# USB.net
KiCad netlist of a schematic drawn in Altium Designer
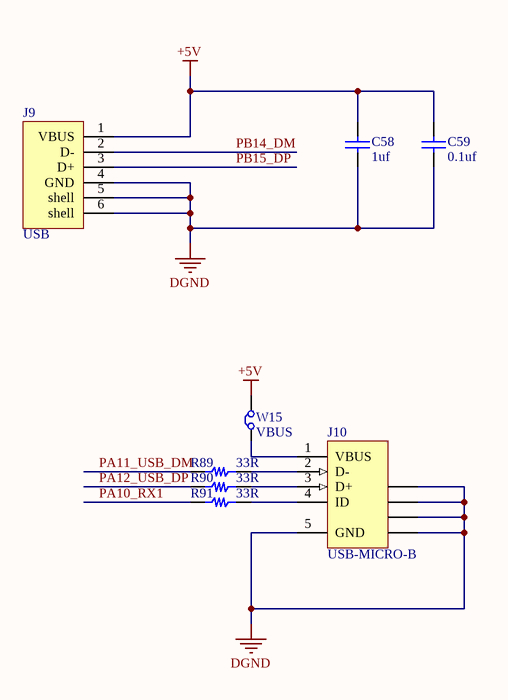
[diagram p0: USB.SchDoc]

(export (version "E")
  (design (tool "Eeschema 10.0.6"))
  (components
    (comp (ref "C58")
      (value "1uf")
      (footprint "0805C")
      (description "贴片电容")
      (fields (field (name "PUBLISHER") "Altium Limited"))
      (libsource (lib "Device_CHT") (part "Cap"))
    )
    (comp (ref "C59")
      (value "0.1uf")
      (footprint "0805C")
      (description "贴片电容")
      (fields (field (name "PUBLISHER") "Altium Limited"))
      (libsource (lib "Device_CHT") (part "Cap"))
    )
    (comp (ref "J9") (value "USB") (footprint "USB-A") (libsource (lib "Connector_Veiko") (part "USB")))
    (comp (ref "J10")
      (value "USB-MICRO-B")
      (footprint "USB-MINI-B")
      (libsource (lib "Connector_Veiko") (part "USB-MICRO-B"))
    )
    (comp (ref "R89")
      (value "33R")
      (footprint "0805_small")
      (description "电阻")
      (fields (field (name "PUBLISHER") "Altium Limited"))
      (libsource (lib "Device_CHT") (part "Res"))
    )
    (comp (ref "R90")
      (value "33R")
      (footprint "0805_small")
      (description "电阻")
      (fields (field (name "PUBLISHER") "Altium Limited"))
      (libsource (lib "Device_CHT") (part "Res"))
    )
    (comp (ref "R91")
      (value "33R")
      (footprint "0805_small")
      (description "电阻")
      (fields (field (name "PUBLISHER") "Altium Limited"))
      (libsource (lib "Device_CHT") (part "Res"))
    )
    (comp (ref "W15")
      (value "VBUS")
      (footprint "sip2-2.54mm")
      (description "Jumper Wire")
      (fields (field (name "PUBLISHER") "Altium Limited"))
      (libsource (lib "Connector_Veiko") (part "Jumper"))
    )
  )
  (nets
    (net (code "1") (name "+5V") (class "Default")
      (node (ref "C58") (pin "1") (pinfunction "1_1") (pintype "passive"))
      (node (ref "C59") (pin "1") (pinfunction "1_1") (pintype "passive"))
      (node (ref "J9") (pin "1") (pinfunction "VBUS_1") (pintype "passive"))
      (node (ref "W15") (pin "2") (pinfunction "C2_2") (pintype "passive"))
    )
    (net (code "2") (name "/PA10_RX1") (class "Default")
      (node (ref "R91") (pin "2") (pinfunction "2_2") (pintype "passive"))
    )
    (net (code "3") (name "/PA11_USB_DM") (class "Default")
      (node (ref "R89") (pin "2") (pinfunction "2_2") (pintype "passive"))
    )
    (net (code "4") (name "/PA12_USB_DP") (class "Default")
      (node (ref "R90") (pin "2") (pinfunction "2_2") (pintype "passive"))
    )
    (net (code "5") (name "/PB14_DM") (class "Default")
      (node (ref "J9") (pin "2") (pinfunction "D-_2") (pintype "passive"))
    )
    (net (code "6") (name "/PB15_DP") (class "Default")
      (node (ref "J9") (pin "3") (pinfunction "D+_3") (pintype "passive"))
    )
    (net (code "7") (name "DGND") (class "Default")
      (node (ref "C58") (pin "2") (pinfunction "2_2") (pintype "passive"))
      (node (ref "C59") (pin "2") (pinfunction "2_2") (pintype "passive"))
      (node (ref "J10") (pin "5") (pinfunction "GND_5") (pintype "passive"))
      (node (ref "J10") (pin "6") (pinfunction "SHLD_6") (pintype "passive"))
      (node (ref "J10") (pin "7") (pinfunction "SHLD_7") (pintype "passive"))
      (node (ref "J10") (pin "8") (pinfunction "SHLD_8") (pintype "passive"))
      (node (ref "J10") (pin "9") (pinfunction "SHLD_9") (pintype "passive"))
      (node (ref "J9") (pin "4") (pinfunction "GND_4") (pintype "passive"))
      (node (ref "J9") (pin "5") (pinfunction "shell_5") (pintype "passive"))
      (node (ref "J9") (pin "6") (pinfunction "shell_6") (pintype "passive"))
    )
    (net (code "8") (name "Net-(J10-D+)") (class "Default")
      (node (ref "J10") (pin "3") (pinfunction "D+_3") (pintype "input"))
      (node (ref "R90") (pin "1") (pinfunction "1_1") (pintype "passive"))
    )
    (net (code "9") (name "Net-(J10-D-)") (class "Default")
      (node (ref "J10") (pin "2") (pinfunction "D-_2") (pintype "input"))
      (node (ref "R89") (pin "1") (pinfunction "1_1") (pintype "passive"))
    )
    (net (code "10") (name "Net-(J10-ID)") (class "Default")
      (node (ref "J10") (pin "4") (pinfunction "ID_4") (pintype "power_in"))
      (node (ref "R91") (pin "1") (pinfunction "1_1") (pintype "passive"))
    )
    (net (code "11") (name "Net-(J10-VBUS)") (class "Default")
      (node (ref "J10") (pin "1") (pinfunction "VBUS_1") (pintype "power_in"))
      (node (ref "W15") (pin "1") (pinfunction "C1_1") (pintype "passive"))
    )
  )
)
